# pds.net
KiCad netlist of a schematic drawn in Altium Designer
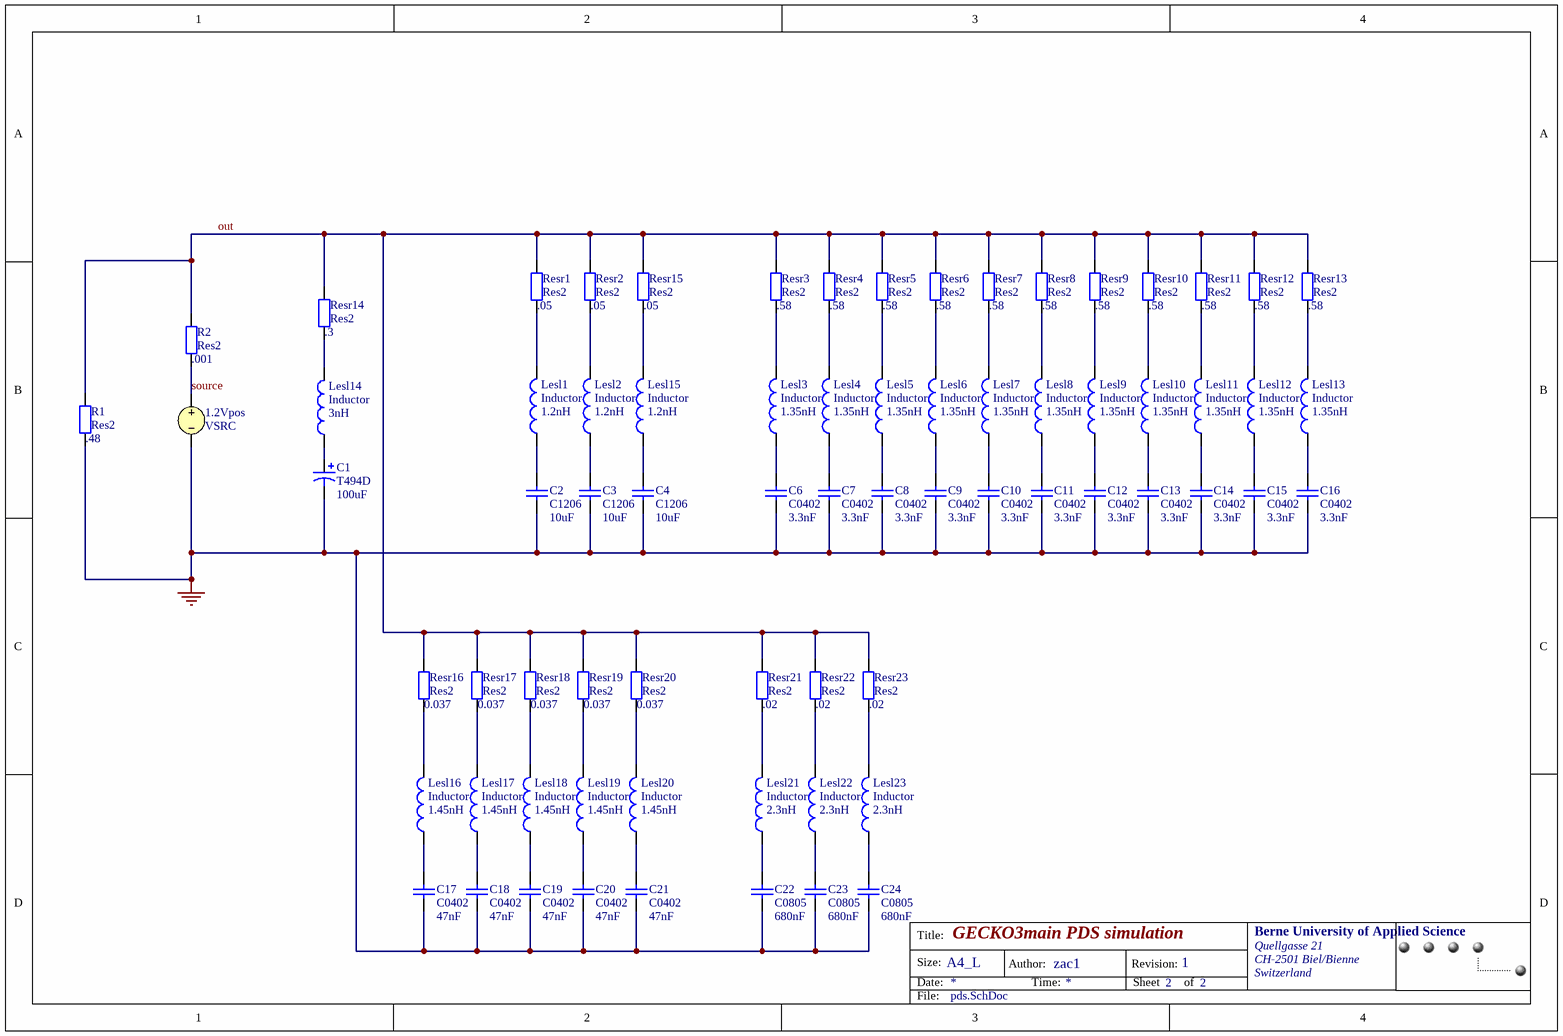
[diagram p0: pds.SchDoc]

(export (version "E")
  (design (tool "Eeschema 10.0.6"))
  (components
    (comp (ref "1.2Vpos")
      (value "VSRC")
      (description "Voltage Source")
      (fields (field (name "PUBLISHER") "Altium Limited"))
      (libsource (lib "Simulation Sources") (part "VSRC"))
    )
    (comp (ref "C1")
      (value "T494D")
      (footprint "D")
      (description "Solid Tantalum Chip Capacitor, Standard T494 Series - Low ESR, Industrial Grade")
      (fields (field (name "ALTIUM_VALUE") "100uF") (field (name "PUBLISHER") "Altium Limited"))
      (libsource (lib "KEMET Chip Capacitor") (part "T494D"))
    )
    (comp (ref "C2")
      (value "C1206")
      (footprint "1206")
      (description "Ceramic Chip Capacitor - Standard")
      (fields (field (name "ALTIUM_VALUE") "10uF") (field (name "PUBLISHER") "Altium Limited"))
      (libsource (lib "KEMET Chip Capacitor") (part "C1206"))
    )
    (comp (ref "C3")
      (value "C1206")
      (footprint "1206")
      (description "Ceramic Chip Capacitor - Standard")
      (fields (field (name "ALTIUM_VALUE") "10uF") (field (name "PUBLISHER") "Altium Limited"))
      (libsource (lib "KEMET Chip Capacitor") (part "C1206"))
    )
    (comp (ref "C4")
      (value "C1206")
      (footprint "1206")
      (description "Ceramic Chip Capacitor - Standard")
      (fields (field (name "ALTIUM_VALUE") "10uF") (field (name "PUBLISHER") "Altium Limited"))
      (libsource (lib "KEMET Chip Capacitor") (part "C1206"))
    )
    (comp (ref "C6")
      (value "C0402")
      (footprint "0402")
      (description "Ceramic Chip Capacitor - Standard")
      (fields (field (name "ALTIUM_VALUE") "3.3nF") (field (name "PUBLISHER") "Altium Limited"))
      (libsource (lib "KEMET Chip Capacitor") (part "C0402"))
    )
    (comp (ref "C7")
      (value "C0402")
      (footprint "0402")
      (description "Ceramic Chip Capacitor - Standard")
      (fields (field (name "ALTIUM_VALUE") "3.3nF") (field (name "PUBLISHER") "Altium Limited"))
      (libsource (lib "KEMET Chip Capacitor") (part "C0402"))
    )
    (comp (ref "C8")
      (value "C0402")
      (footprint "0402")
      (description "Ceramic Chip Capacitor - Standard")
      (fields (field (name "ALTIUM_VALUE") "3.3nF") (field (name "PUBLISHER") "Altium Limited"))
      (libsource (lib "KEMET Chip Capacitor") (part "C0402"))
    )
    (comp (ref "C9")
      (value "C0402")
      (footprint "0402")
      (description "Ceramic Chip Capacitor - Standard")
      (fields (field (name "ALTIUM_VALUE") "3.3nF") (field (name "PUBLISHER") "Altium Limited"))
      (libsource (lib "KEMET Chip Capacitor") (part "C0402"))
    )
    (comp (ref "C10")
      (value "C0402")
      (footprint "0402")
      (description "Ceramic Chip Capacitor - Standard")
      (fields (field (name "ALTIUM_VALUE") "3.3nF") (field (name "PUBLISHER") "Altium Limited"))
      (libsource (lib "KEMET Chip Capacitor") (part "C0402"))
    )
    (comp (ref "C11")
      (value "C0402")
      (footprint "0402")
      (description "Ceramic Chip Capacitor - Standard")
      (fields (field (name "ALTIUM_VALUE") "3.3nF") (field (name "PUBLISHER") "Altium Limited"))
      (libsource (lib "KEMET Chip Capacitor") (part "C0402"))
    )
    (comp (ref "C12")
      (value "C0402")
      (footprint "0402")
      (description "Ceramic Chip Capacitor - Standard")
      (fields (field (name "ALTIUM_VALUE") "3.3nF") (field (name "PUBLISHER") "Altium Limited"))
      (libsource (lib "KEMET Chip Capacitor") (part "C0402"))
    )
    (comp (ref "C13")
      (value "C0402")
      (footprint "0402")
      (description "Ceramic Chip Capacitor - Standard")
      (fields (field (name "ALTIUM_VALUE") "3.3nF") (field (name "PUBLISHER") "Altium Limited"))
      (libsource (lib "KEMET Chip Capacitor") (part "C0402"))
    )
    (comp (ref "C14")
      (value "C0402")
      (footprint "0402")
      (description "Ceramic Chip Capacitor - Standard")
      (fields (field (name "ALTIUM_VALUE") "3.3nF") (field (name "PUBLISHER") "Altium Limited"))
      (libsource (lib "KEMET Chip Capacitor") (part "C0402"))
    )
    (comp (ref "C15")
      (value "C0402")
      (footprint "0402")
      (description "Ceramic Chip Capacitor - Standard")
      (fields (field (name "ALTIUM_VALUE") "3.3nF") (field (name "PUBLISHER") "Altium Limited"))
      (libsource (lib "KEMET Chip Capacitor") (part "C0402"))
    )
    (comp (ref "C16")
      (value "C0402")
      (footprint "0402")
      (description "Ceramic Chip Capacitor - Standard")
      (fields (field (name "ALTIUM_VALUE") "3.3nF") (field (name "PUBLISHER") "Altium Limited"))
      (libsource (lib "KEMET Chip Capacitor") (part "C0402"))
    )
    (comp (ref "C17")
      (value "C0402")
      (footprint "0402")
      (description "Ceramic Chip Capacitor - Standard")
      (fields (field (name "ALTIUM_VALUE") "47nF") (field (name "PUBLISHER") "Altium Limited"))
      (libsource (lib "KEMET Chip Capacitor") (part "C0402"))
    )
    (comp (ref "C18")
      (value "C0402")
      (footprint "0402")
      (description "Ceramic Chip Capacitor - Standard")
      (fields (field (name "ALTIUM_VALUE") "47nF") (field (name "PUBLISHER") "Altium Limited"))
      (libsource (lib "KEMET Chip Capacitor") (part "C0402"))
    )
    (comp (ref "C19")
      (value "C0402")
      (footprint "0402")
      (description "Ceramic Chip Capacitor - Standard")
      (fields (field (name "ALTIUM_VALUE") "47nF") (field (name "PUBLISHER") "Altium Limited"))
      (libsource (lib "KEMET Chip Capacitor") (part "C0402"))
    )
    (comp (ref "C20")
      (value "C0402")
      (footprint "0402")
      (description "Ceramic Chip Capacitor - Standard")
      (fields (field (name "ALTIUM_VALUE") "47nF") (field (name "PUBLISHER") "Altium Limited"))
      (libsource (lib "KEMET Chip Capacitor") (part "C0402"))
    )
    (comp (ref "C21")
      (value "C0402")
      (footprint "0402")
      (description "Ceramic Chip Capacitor - Standard")
      (fields (field (name "ALTIUM_VALUE") "47nF") (field (name "PUBLISHER") "Altium Limited"))
      (libsource (lib "KEMET Chip Capacitor") (part "C0402"))
    )
    (comp (ref "C22")
      (value "C0805")
      (footprint "0805")
      (description "Ceramic Chip Capacitor - Standard")
      (fields (field (name "ALTIUM_VALUE") "680nF") (field (name "PUBLISHER") "Altium Limited"))
      (libsource (lib "KEMET Chip Capacitor") (part "C0805"))
    )
    (comp (ref "C23")
      (value "C0805")
      (footprint "0805")
      (description "Ceramic Chip Capacitor - Standard")
      (fields (field (name "ALTIUM_VALUE") "680nF") (field (name "PUBLISHER") "Altium Limited"))
      (libsource (lib "KEMET Chip Capacitor") (part "C0805"))
    )
    (comp (ref "C24")
      (value "C0805")
      (footprint "0805")
      (description "Ceramic Chip Capacitor - Standard")
      (fields (field (name "ALTIUM_VALUE") "680nF") (field (name "PUBLISHER") "Altium Limited"))
      (libsource (lib "KEMET Chip Capacitor") (part "C0805"))
    )
    (comp (ref "Lesl1")
      (value "Inductor")
      (footprint "INDC1005-0402")
      (fields (field (name "ALTIUM_VALUE") "1.2nH") (field (name "PUBLISHER") "Altium Limited"))
      (libsource (lib "Miscellaneous Devices") (part "Inductor"))
    )
    (comp (ref "Lesl2")
      (value "Inductor")
      (footprint "INDC1005-0402")
      (fields (field (name "ALTIUM_VALUE") "1.2nH") (field (name "PUBLISHER") "Altium Limited"))
      (libsource (lib "Miscellaneous Devices") (part "Inductor"))
    )
    (comp (ref "Lesl3")
      (value "Inductor")
      (footprint "INDC1005-0402")
      (fields (field (name "ALTIUM_VALUE") "1.35nH") (field (name "PUBLISHER") "Altium Limited"))
      (libsource (lib "Miscellaneous Devices") (part "Inductor"))
    )
    (comp (ref "Lesl4")
      (value "Inductor")
      (footprint "INDC1005-0402")
      (fields (field (name "ALTIUM_VALUE") "1.35nH") (field (name "PUBLISHER") "Altium Limited"))
      (libsource (lib "Miscellaneous Devices") (part "Inductor"))
    )
    (comp (ref "Lesl5")
      (value "Inductor")
      (footprint "INDC1005-0402")
      (fields (field (name "ALTIUM_VALUE") "1.35nH") (field (name "PUBLISHER") "Altium Limited"))
      (libsource (lib "Miscellaneous Devices") (part "Inductor"))
    )
    (comp (ref "Lesl6")
      (value "Inductor")
      (footprint "INDC1005-0402")
      (fields (field (name "ALTIUM_VALUE") "1.35nH") (field (name "PUBLISHER") "Altium Limited"))
      (libsource (lib "Miscellaneous Devices") (part "Inductor"))
    )
    (comp (ref "Lesl7")
      (value "Inductor")
      (footprint "INDC1005-0402")
      (fields (field (name "ALTIUM_VALUE") "1.35nH") (field (name "PUBLISHER") "Altium Limited"))
      (libsource (lib "Miscellaneous Devices") (part "Inductor"))
    )
    (comp (ref "Lesl8")
      (value "Inductor")
      (footprint "INDC1005-0402")
      (fields (field (name "ALTIUM_VALUE") "1.35nH") (field (name "PUBLISHER") "Altium Limited"))
      (libsource (lib "Miscellaneous Devices") (part "Inductor"))
    )
    (comp (ref "Lesl9")
      (value "Inductor")
      (footprint "INDC1005-0402")
      (fields (field (name "ALTIUM_VALUE") "1.35nH") (field (name "PUBLISHER") "Altium Limited"))
      (libsource (lib "Miscellaneous Devices") (part "Inductor"))
    )
    (comp (ref "Lesl10")
      (value "Inductor")
      (footprint "INDC1005-0402")
      (fields (field (name "ALTIUM_VALUE") "1.35nH") (field (name "PUBLISHER") "Altium Limited"))
      (libsource (lib "Miscellaneous Devices") (part "Inductor"))
    )
    (comp (ref "Lesl11")
      (value "Inductor")
      (footprint "INDC1005-0402")
      (fields (field (name "ALTIUM_VALUE") "1.35nH") (field (name "PUBLISHER") "Altium Limited"))
      (libsource (lib "Miscellaneous Devices") (part "Inductor"))
    )
    (comp (ref "Lesl12")
      (value "Inductor")
      (footprint "INDC1005-0402")
      (fields (field (name "ALTIUM_VALUE") "1.35nH") (field (name "PUBLISHER") "Altium Limited"))
      (libsource (lib "Miscellaneous Devices") (part "Inductor"))
    )
    (comp (ref "Lesl13")
      (value "Inductor")
      (footprint "INDC1005-0402")
      (fields (field (name "ALTIUM_VALUE") "1.35nH") (field (name "PUBLISHER") "Altium Limited"))
      (libsource (lib "Miscellaneous Devices") (part "Inductor"))
    )
    (comp (ref "Lesl14")
      (value "Inductor")
      (footprint "INDC1005-0402")
      (fields (field (name "ALTIUM_VALUE") "3nH") (field (name "PUBLISHER") "Altium Limited"))
      (libsource (lib "Miscellaneous Devices") (part "Inductor"))
    )
    (comp (ref "Lesl15")
      (value "Inductor")
      (footprint "INDC1005-0402")
      (fields (field (name "ALTIUM_VALUE") "1.2nH") (field (name "PUBLISHER") "Altium Limited"))
      (libsource (lib "Miscellaneous Devices") (part "Inductor"))
    )
    (comp (ref "Lesl16")
      (value "Inductor")
      (footprint "INDC1005-0402")
      (fields (field (name "ALTIUM_VALUE") "1.45nH") (field (name "PUBLISHER") "Altium Limited"))
      (libsource (lib "Miscellaneous Devices") (part "Inductor"))
    )
    (comp (ref "Lesl17")
      (value "Inductor")
      (footprint "INDC1005-0402")
      (fields (field (name "ALTIUM_VALUE") "1.45nH") (field (name "PUBLISHER") "Altium Limited"))
      (libsource (lib "Miscellaneous Devices") (part "Inductor"))
    )
    (comp (ref "Lesl18")
      (value "Inductor")
      (footprint "INDC1005-0402")
      (fields (field (name "ALTIUM_VALUE") "1.45nH") (field (name "PUBLISHER") "Altium Limited"))
      (libsource (lib "Miscellaneous Devices") (part "Inductor"))
    )
    (comp (ref "Lesl19")
      (value "Inductor")
      (footprint "INDC1005-0402")
      (fields (field (name "ALTIUM_VALUE") "1.45nH") (field (name "PUBLISHER") "Altium Limited"))
      (libsource (lib "Miscellaneous Devices") (part "Inductor"))
    )
    (comp (ref "Lesl20")
      (value "Inductor")
      (footprint "INDC1005-0402")
      (fields (field (name "ALTIUM_VALUE") "1.45nH") (field (name "PUBLISHER") "Altium Limited"))
      (libsource (lib "Miscellaneous Devices") (part "Inductor"))
    )
    (comp (ref "Lesl21")
      (value "Inductor")
      (footprint "INDC1005-0402")
      (fields (field (name "ALTIUM_VALUE") "2.3nH") (field (name "PUBLISHER") "Altium Limited"))
      (libsource (lib "Miscellaneous Devices") (part "Inductor"))
    )
    (comp (ref "Lesl22")
      (value "Inductor")
      (footprint "INDC1005-0402")
      (fields (field (name "ALTIUM_VALUE") "2.3nH") (field (name "PUBLISHER") "Altium Limited"))
      (libsource (lib "Miscellaneous Devices") (part "Inductor"))
    )
    (comp (ref "Lesl23")
      (value "Inductor")
      (footprint "INDC1005-0402")
      (fields (field (name "ALTIUM_VALUE") "2.3nH") (field (name "PUBLISHER") "Altium Limited"))
      (libsource (lib "Miscellaneous Devices") (part "Inductor"))
    )
    (comp (ref "R1")
      (value "Res2")
      (footprint "AXIAL-0.4")
      (description "Resistor")
      (fields (field (name "ALTIUM_VALUE") ".48") (field (name "PUBLISHER") "Altium Limited"))
      (libsource (lib "Miscellaneous Devices") (part "Res2"))
    )
    (comp (ref "R2")
      (value "Res2")
      (footprint "AXIAL-0.4")
      (description "Resistor")
      (fields (field (name "ALTIUM_VALUE") ".001") (field (name "PUBLISHER") "Altium Limited"))
      (libsource (lib "Miscellaneous Devices") (part "Res2"))
    )
    (comp (ref "Resr1")
      (value "Res2")
      (footprint "AXIAL-0.4")
      (description "Resistor")
      (fields (field (name "ALTIUM_VALUE") ".05") (field (name "PUBLISHER") "Altium Limited"))
      (libsource (lib "Miscellaneous Devices") (part "Res2"))
    )
    (comp (ref "Resr2")
      (value "Res2")
      (footprint "AXIAL-0.4")
      (description "Resistor")
      (fields (field (name "ALTIUM_VALUE") ".05") (field (name "PUBLISHER") "Altium Limited"))
      (libsource (lib "Miscellaneous Devices") (part "Res2"))
    )
    (comp (ref "Resr3")
      (value "Res2")
      (footprint "AXIAL-0.4")
      (description "Resistor")
      (fields (field (name "ALTIUM_VALUE") ".58") (field (name "PUBLISHER") "Altium Limited"))
      (libsource (lib "Miscellaneous Devices") (part "Res2"))
    )
    (comp (ref "Resr4")
      (value "Res2")
      (footprint "AXIAL-0.4")
      (description "Resistor")
      (fields (field (name "ALTIUM_VALUE") ".58") (field (name "PUBLISHER") "Altium Limited"))
      (libsource (lib "Miscellaneous Devices") (part "Res2"))
    )
    (comp (ref "Resr5")
      (value "Res2")
      (footprint "AXIAL-0.4")
      (description "Resistor")
      (fields (field (name "ALTIUM_VALUE") ".58") (field (name "PUBLISHER") "Altium Limited"))
      (libsource (lib "Miscellaneous Devices") (part "Res2"))
    )
    (comp (ref "Resr6")
      (value "Res2")
      (footprint "AXIAL-0.4")
      (description "Resistor")
      (fields (field (name "ALTIUM_VALUE") ".58") (field (name "PUBLISHER") "Altium Limited"))
      (libsource (lib "Miscellaneous Devices") (part "Res2"))
    )
    (comp (ref "Resr7")
      (value "Res2")
      (footprint "AXIAL-0.4")
      (description "Resistor")
      (fields (field (name "ALTIUM_VALUE") ".58") (field (name "PUBLISHER") "Altium Limited"))
      (libsource (lib "Miscellaneous Devices") (part "Res2"))
    )
    (comp (ref "Resr8")
      (value "Res2")
      (footprint "AXIAL-0.4")
      (description "Resistor")
      (fields (field (name "ALTIUM_VALUE") ".58") (field (name "PUBLISHER") "Altium Limited"))
      (libsource (lib "Miscellaneous Devices") (part "Res2"))
    )
    (comp (ref "Resr9")
      (value "Res2")
      (footprint "AXIAL-0.4")
      (description "Resistor")
      (fields (field (name "ALTIUM_VALUE") ".58") (field (name "PUBLISHER") "Altium Limited"))
      (libsource (lib "Miscellaneous Devices") (part "Res2"))
    )
    (comp (ref "Resr10")
      (value "Res2")
      (footprint "AXIAL-0.4")
      (description "Resistor")
      (fields (field (name "ALTIUM_VALUE") ".58") (field (name "PUBLISHER") "Altium Limited"))
      (libsource (lib "Miscellaneous Devices") (part "Res2"))
    )
    (comp (ref "Resr11")
      (value "Res2")
      (footprint "AXIAL-0.4")
      (description "Resistor")
      (fields (field (name "ALTIUM_VALUE") ".58") (field (name "PUBLISHER") "Altium Limited"))
      (libsource (lib "Miscellaneous Devices") (part "Res2"))
    )
    (comp (ref "Resr12")
      (value "Res2")
      (footprint "AXIAL-0.4")
      (description "Resistor")
      (fields (field (name "ALTIUM_VALUE") ".58") (field (name "PUBLISHER") "Altium Limited"))
      (libsource (lib "Miscellaneous Devices") (part "Res2"))
    )
    (comp (ref "Resr13")
      (value "Res2")
      (footprint "AXIAL-0.4")
      (description "Resistor")
      (fields (field (name "ALTIUM_VALUE") ".58") (field (name "PUBLISHER") "Altium Limited"))
      (libsource (lib "Miscellaneous Devices") (part "Res2"))
    )
    (comp (ref "Resr14")
      (value "Res2")
      (footprint "AXIAL-0.4")
      (description "Resistor")
      (fields (field (name "ALTIUM_VALUE") ".3") (field (name "PUBLISHER") "Altium Limited"))
      (libsource (lib "Miscellaneous Devices") (part "Res2"))
    )
    (comp (ref "Resr15")
      (value "Res2")
      (footprint "AXIAL-0.4")
      (description "Resistor")
      (fields (field (name "ALTIUM_VALUE") ".05") (field (name "PUBLISHER") "Altium Limited"))
      (libsource (lib "Miscellaneous Devices") (part "Res2"))
    )
    (comp (ref "Resr16")
      (value "Res2")
      (footprint "AXIAL-0.4")
      (description "Resistor")
      (fields (field (name "ALTIUM_VALUE") "0.037") (field (name "PUBLISHER") "Altium Limited"))
      (libsource (lib "Miscellaneous Devices") (part "Res2"))
    )
    (comp (ref "Resr17")
      (value "Res2")
      (footprint "AXIAL-0.4")
      (description "Resistor")
      (fields (field (name "ALTIUM_VALUE") "0.037") (field (name "PUBLISHER") "Altium Limited"))
      (libsource (lib "Miscellaneous Devices") (part "Res2"))
    )
    (comp (ref "Resr18")
      (value "Res2")
      (footprint "AXIAL-0.4")
      (description "Resistor")
      (fields (field (name "ALTIUM_VALUE") "0.037") (field (name "PUBLISHER") "Altium Limited"))
      (libsource (lib "Miscellaneous Devices") (part "Res2"))
    )
    (comp (ref "Resr19")
      (value "Res2")
      (footprint "AXIAL-0.4")
      (description "Resistor")
      (fields (field (name "ALTIUM_VALUE") "0.037") (field (name "PUBLISHER") "Altium Limited"))
      (libsource (lib "Miscellaneous Devices") (part "Res2"))
    )
    (comp (ref "Resr20")
      (value "Res2")
      (footprint "AXIAL-0.4")
      (description "Resistor")
      (fields (field (name "ALTIUM_VALUE") "0.037") (field (name "PUBLISHER") "Altium Limited"))
      (libsource (lib "Miscellaneous Devices") (part "Res2"))
    )
    (comp (ref "Resr21")
      (value "Res2")
      (footprint "AXIAL-0.4")
      (description "Resistor")
      (fields (field (name "ALTIUM_VALUE") ".02") (field (name "PUBLISHER") "Altium Limited"))
      (libsource (lib "Miscellaneous Devices") (part "Res2"))
    )
    (comp (ref "Resr22")
      (value "Res2")
      (footprint "AXIAL-0.4")
      (description "Resistor")
      (fields (field (name "ALTIUM_VALUE") ".02") (field (name "PUBLISHER") "Altium Limited"))
      (libsource (lib "Miscellaneous Devices") (part "Res2"))
    )
    (comp (ref "Resr23")
      (value "Res2")
      (footprint "AXIAL-0.4")
      (description "Resistor")
      (fields (field (name "ALTIUM_VALUE") ".02") (field (name "PUBLISHER") "Altium Limited"))
      (libsource (lib "Miscellaneous Devices") (part "Res2"))
    )
  )
  (nets
    (net (code "1") (name "/out") (class "Default")
      (node (ref "R1") (pin "2") (pinfunction "2_2") (pintype "passive"))
      (node (ref "R2") (pin "2") (pinfunction "2_2") (pintype "passive"))
      (node (ref "Resr1") (pin "2") (pinfunction "2_2") (pintype "passive"))
      (node (ref "Resr10") (pin "2") (pinfunction "2_2") (pintype "passive"))
      (node (ref "Resr11") (pin "2") (pinfunction "2_2") (pintype "passive"))
      (node (ref "Resr12") (pin "2") (pinfunction "2_2") (pintype "passive"))
      (node (ref "Resr13") (pin "2") (pinfunction "2_2") (pintype "passive"))
      (node (ref "Resr14") (pin "2") (pinfunction "2_2") (pintype "passive"))
      (node (ref "Resr15") (pin "2") (pinfunction "2_2") (pintype "passive"))
      (node (ref "Resr16") (pin "2") (pinfunction "2_2") (pintype "passive"))
      (node (ref "Resr17") (pin "2") (pinfunction "2_2") (pintype "passive"))
      (node (ref "Resr18") (pin "2") (pinfunction "2_2") (pintype "passive"))
      (node (ref "Resr19") (pin "2") (pinfunction "2_2") (pintype "passive"))
      (node (ref "Resr2") (pin "2") (pinfunction "2_2") (pintype "passive"))
      (node (ref "Resr20") (pin "2") (pinfunction "2_2") (pintype "passive"))
      (node (ref "Resr21") (pin "2") (pinfunction "2_2") (pintype "passive"))
      (node (ref "Resr22") (pin "2") (pinfunction "2_2") (pintype "passive"))
      (node (ref "Resr23") (pin "2") (pinfunction "2_2") (pintype "passive"))
      (node (ref "Resr3") (pin "2") (pinfunction "2_2") (pintype "passive"))
      (node (ref "Resr4") (pin "2") (pinfunction "2_2") (pintype "passive"))
      (node (ref "Resr5") (pin "2") (pinfunction "2_2") (pintype "passive"))
      (node (ref "Resr6") (pin "2") (pinfunction "2_2") (pintype "passive"))
      (node (ref "Resr7") (pin "2") (pinfunction "2_2") (pintype "passive"))
      (node (ref "Resr8") (pin "2") (pinfunction "2_2") (pintype "passive"))
      (node (ref "Resr9") (pin "2") (pinfunction "2_2") (pintype "passive"))
    )
    (net (code "2") (name "/source") (class "Default")
      (node (ref "1.2Vpos") (pin "1") (pinfunction "1_1") (pintype "passive"))
      (node (ref "R2") (pin "1") (pinfunction "1_1") (pintype "passive"))
    )
    (net (code "3") (name "GND") (class "Default")
      (node (ref "1.2Vpos") (pin "2") (pinfunction "2_2") (pintype "passive"))
      (node (ref "C1") (pin "2") (pinfunction "2_2") (pintype "passive"))
      (node (ref "C10") (pin "1") (pinfunction "1_1") (pintype "passive"))
      (node (ref "C11") (pin "1") (pinfunction "1_1") (pintype "passive"))
      (node (ref "C12") (pin "1") (pinfunction "1_1") (pintype "passive"))
      (node (ref "C13") (pin "1") (pinfunction "1_1") (pintype "passive"))
      (node (ref "C14") (pin "1") (pinfunction "1_1") (pintype "passive"))
      (node (ref "C15") (pin "1") (pinfunction "1_1") (pintype "passive"))
      (node (ref "C16") (pin "1") (pinfunction "1_1") (pintype "passive"))
      (node (ref "C17") (pin "1") (pinfunction "1_1") (pintype "passive"))
      (node (ref "C18") (pin "1") (pinfunction "1_1") (pintype "passive"))
      (node (ref "C19") (pin "1") (pinfunction "1_1") (pintype "passive"))
      (node (ref "C2") (pin "1") (pinfunction "1_1") (pintype "passive"))
      (node (ref "C20") (pin "1") (pinfunction "1_1") (pintype "passive"))
      (node (ref "C21") (pin "1") (pinfunction "1_1") (pintype "passive"))
      (node (ref "C22") (pin "1") (pinfunction "1_1") (pintype "passive"))
      (node (ref "C23") (pin "1") (pinfunction "1_1") (pintype "passive"))
      (node (ref "C24") (pin "1") (pinfunction "1_1") (pintype "passive"))
      (node (ref "C3") (pin "1") (pinfunction "1_1") (pintype "passive"))
      (node (ref "C4") (pin "1") (pinfunction "1_1") (pintype "passive"))
      (node (ref "C6") (pin "1") (pinfunction "1_1") (pintype "passive"))
      (node (ref "C7") (pin "1") (pinfunction "1_1") (pintype "passive"))
      (node (ref "C8") (pin "1") (pinfunction "1_1") (pintype "passive"))
      (node (ref "C9") (pin "1") (pinfunction "1_1") (pintype "passive"))
      (node (ref "R1") (pin "1") (pinfunction "1_1") (pintype "passive"))
    )
    (net (code "4") (name "Net-(C1-Pad1)") (class "Default")
      (node (ref "C1") (pin "1") (pinfunction "1_1") (pintype "passive"))
      (node (ref "Lesl14") (pin "1") (pinfunction "1_1") (pintype "passive"))
    )
    (net (code "5") (name "Net-(C2-Pad2)") (class "Default")
      (node (ref "C2") (pin "2") (pinfunction "2_2") (pintype "passive"))
      (node (ref "Lesl1") (pin "1") (pinfunction "1_1") (pintype "passive"))
    )
    (net (code "6") (name "Net-(C3-Pad2)") (class "Default")
      (node (ref "C3") (pin "2") (pinfunction "2_2") (pintype "passive"))
      (node (ref "Lesl2") (pin "1") (pinfunction "1_1") (pintype "passive"))
    )
    (net (code "7") (name "Net-(C4-Pad2)") (class "Default")
      (node (ref "C4") (pin "2") (pinfunction "2_2") (pintype "passive"))
      (node (ref "Lesl15") (pin "1") (pinfunction "1_1") (pintype "passive"))
    )
    (net (code "8") (name "Net-(C6-Pad2)") (class "Default")
      (node (ref "C6") (pin "2") (pinfunction "2_2") (pintype "passive"))
      (node (ref "Lesl3") (pin "1") (pinfunction "1_1") (pintype "passive"))
    )
    (net (code "9") (name "Net-(C7-Pad2)") (class "Default")
      (node (ref "C7") (pin "2") (pinfunction "2_2") (pintype "passive"))
      (node (ref "Lesl4") (pin "1") (pinfunction "1_1") (pintype "passive"))
    )
    (net (code "10") (name "Net-(C8-Pad2)") (class "Default")
      (node (ref "C8") (pin "2") (pinfunction "2_2") (pintype "passive"))
      (node (ref "Lesl5") (pin "1") (pinfunction "1_1") (pintype "passive"))
    )
    (net (code "11") (name "Net-(C9-Pad2)") (class "Default")
      (node (ref "C9") (pin "2") (pinfunction "2_2") (pintype "passive"))
      (node (ref "Lesl6") (pin "1") (pinfunction "1_1") (pintype "passive"))
    )
    (net (code "12") (name "Net-(C10-Pad2)") (class "Default")
      (node (ref "C10") (pin "2") (pinfunction "2_2") (pintype "passive"))
      (node (ref "Lesl7") (pin "1") (pinfunction "1_1") (pintype "passive"))
    )
    (net (code "13") (name "Net-(C11-Pad2)") (class "Default")
      (node (ref "C11") (pin "2") (pinfunction "2_2") (pintype "passive"))
      (node (ref "Lesl8") (pin "1") (pinfunction "1_1") (pintype "passive"))
    )
    (net (code "14") (name "Net-(C12-Pad2)") (class "Default")
      (node (ref "C12") (pin "2") (pinfunction "2_2") (pintype "passive"))
      (node (ref "Lesl9") (pin "1") (pinfunction "1_1") (pintype "passive"))
    )
    (net (code "15") (name "Net-(C13-Pad2)") (class "Default")
      (node (ref "C13") (pin "2") (pinfunction "2_2") (pintype "passive"))
      (node (ref "Lesl10") (pin "1") (pinfunction "1_1") (pintype "passive"))
    )
    (net (code "16") (name "Net-(C14-Pad2)") (class "Default")
      (node (ref "C14") (pin "2") (pinfunction "2_2") (pintype "passive"))
      (node (ref "Lesl11") (pin "1") (pinfunction "1_1") (pintype "passive"))
    )
    (net (code "17") (name "Net-(C15-Pad2)") (class "Default")
      (node (ref "C15") (pin "2") (pinfunction "2_2") (pintype "passive"))
      (node (ref "Lesl12") (pin "1") (pinfunction "1_1") (pintype "passive"))
    )
    (net (code "18") (name "Net-(C16-Pad2)") (class "Default")
      (node (ref "C16") (pin "2") (pinfunction "2_2") (pintype "passive"))
      (node (ref "Lesl13") (pin "1") (pinfunction "1_1") (pintype "passive"))
    )
    (net (code "19") (name "Net-(C17-Pad2)") (class "Default")
      (node (ref "C17") (pin "2") (pinfunction "2_2") (pintype "passive"))
      (node (ref "Lesl16") (pin "1") (pinfunction "1_1") (pintype "passive"))
    )
    (net (code "20") (name "Net-(C18-Pad2)") (class "Default")
      (node (ref "C18") (pin "2") (pinfunction "2_2") (pintype "passive"))
      (node (ref "Lesl17") (pin "1") (pinfunction "1_1") (pintype "passive"))
    )
    (net (code "21") (name "Net-(C19-Pad2)") (class "Default")
      (node (ref "C19") (pin "2") (pinfunction "2_2") (pintype "passive"))
      (node (ref "Lesl18") (pin "1") (pinfunction "1_1") (pintype "passive"))
    )
    (net (code "22") (name "Net-(C20-Pad2)") (class "Default")
      (node (ref "C20") (pin "2") (pinfunction "2_2") (pintype "passive"))
      (node (ref "Lesl19") (pin "1") (pinfunction "1_1") (pintype "passive"))
    )
    (net (code "23") (name "Net-(C21-Pad2)") (class "Default")
      (node (ref "C21") (pin "2") (pinfunction "2_2") (pintype "passive"))
      (node (ref "Lesl20") (pin "1") (pinfunction "1_1") (pintype "passive"))
    )
    (net (code "24") (name "Net-(C22-Pad2)") (class "Default")
      (node (ref "C22") (pin "2") (pinfunction "2_2") (pintype "passive"))
      (node (ref "Lesl21") (pin "1") (pinfunction "1_1") (pintype "passive"))
    )
    (net (code "25") (name "Net-(C23-Pad2)") (class "Default")
      (node (ref "C23") (pin "2") (pinfunction "2_2") (pintype "passive"))
      (node (ref "Lesl22") (pin "1") (pinfunction "1_1") (pintype "passive"))
    )
    (net (code "26") (name "Net-(C24-Pad2)") (class "Default")
      (node (ref "C24") (pin "2") (pinfunction "2_2") (pintype "passive"))
      (node (ref "Lesl23") (pin "1") (pinfunction "1_1") (pintype "passive"))
    )
    (net (code "27") (name "Net-(Lesl1-Pad2)") (class "Default")
      (node (ref "Lesl1") (pin "2") (pinfunction "2_2") (pintype "passive"))
      (node (ref "Resr1") (pin "1") (pinfunction "1_1") (pintype "passive"))
    )
    (net (code "28") (name "Net-(Lesl2-Pad2)") (class "Default")
      (node (ref "Lesl2") (pin "2") (pinfunction "2_2") (pintype "passive"))
      (node (ref "Resr2") (pin "1") (pinfunction "1_1") (pintype "passive"))
    )
    (net (code "29") (name "Net-(Lesl3-Pad2)") (class "Default")
      (node (ref "Lesl3") (pin "2") (pinfunction "2_2") (pintype "passive"))
      (node (ref "Resr3") (pin "1") (pinfunction "1_1") (pintype "passive"))
    )
    (net (code "30") (name "Net-(Lesl4-Pad2)") (class "Default")
      (node (ref "Lesl4") (pin "2") (pinfunction "2_2") (pintype "passive"))
      (node (ref "Resr4") (pin "1") (pinfunction "1_1") (pintype "passive"))
    )
    (net (code "31") (name "Net-(Lesl5-Pad2)") (class "Default")
      (node (ref "Lesl5") (pin "2") (pinfunction "2_2") (pintype "passive"))
      (node (ref "Resr5") (pin "1") (pinfunction "1_1") (pintype "passive"))
    )
    (net (code "32") (name "Net-(Lesl6-Pad2)") (class "Default")
      (node (ref "Lesl6") (pin "2") (pinfunction "2_2") (pintype "passive"))
      (node (ref "Resr6") (pin "1") (pinfunction "1_1") (pintype "passive"))
    )
    (net (code "33") (name "Net-(Lesl7-Pad2)") (class "Default")
      (node (ref "Lesl7") (pin "2") (pinfunction "2_2") (pintype "passive"))
      (node (ref "Resr7") (pin "1") (pinfunction "1_1") (pintype "passive"))
    )
    (net (code "34") (name "Net-(Lesl8-Pad2)") (class "Default")
      (node (ref "Lesl8") (pin "2") (pinfunction "2_2") (pintype "passive"))
      (node (ref "Resr8") (pin "1") (pinfunction "1_1") (pintype "passive"))
    )
    (net (code "35") (name "Net-(Lesl9-Pad2)") (class "Default")
      (node (ref "Lesl9") (pin "2") (pinfunction "2_2") (pintype "passive"))
      (node (ref "Resr9") (pin "1") (pinfunction "1_1") (pintype "passive"))
    )
    (net (code "36") (name "Net-(Lesl10-Pad2)") (class "Default")
      (node (ref "Lesl10") (pin "2") (pinfunction "2_2") (pintype "passive"))
      (node (ref "Resr10") (pin "1") (pinfunction "1_1") (pintype "passive"))
    )
    (net (code "37") (name "Net-(Lesl11-Pad2)") (class "Default")
      (node (ref "Lesl11") (pin "2") (pinfunction "2_2") (pintype "passive"))
      (node (ref "Resr11") (pin "1") (pinfunction "1_1") (pintype "passive"))
    )
    (net (code "38") (name "Net-(Lesl12-Pad2)") (class "Default")
      (node (ref "Lesl12") (pin "2") (pinfunction "2_2") (pintype "passive"))
      (node (ref "Resr12") (pin "1") (pinfunction "1_1") (pintype "passive"))
    )
    (net (code "39") (name "Net-(Lesl13-Pad2)") (class "Default")
      (node (ref "Lesl13") (pin "2") (pinfunction "2_2") (pintype "passive"))
      (node (ref "Resr13") (pin "1") (pinfunction "1_1") (pintype "passive"))
    )
    (net (code "40") (name "Net-(Lesl14-Pad2)") (class "Default")
      (node (ref "Lesl14") (pin "2") (pinfunction "2_2") (pintype "passive"))
      (node (ref "Resr14") (pin "1") (pinfunction "1_1") (pintype "passive"))
    )
    (net (code "41") (name "Net-(Lesl15-Pad2)") (class "Default")
      (node (ref "Lesl15") (pin "2") (pinfunction "2_2") (pintype "passive"))
      (node (ref "Resr15") (pin "1") (pinfunction "1_1") (pintype "passive"))
    )
    (net (code "42") (name "Net-(Lesl16-Pad2)") (class "Default")
      (node (ref "Lesl16") (pin "2") (pinfunction "2_2") (pintype "passive"))
      (node (ref "Resr16") (pin "1") (pinfunction "1_1") (pintype "passive"))
    )
    (net (code "43") (name "Net-(Lesl17-Pad2)") (class "Default")
      (node (ref "Lesl17") (pin "2") (pinfunction "2_2") (pintype "passive"))
      (node (ref "Resr17") (pin "1") (pinfunction "1_1") (pintype "passive"))
    )
    (net (code "44") (name "Net-(Lesl18-Pad2)") (class "Default")
      (node (ref "Lesl18") (pin "2") (pinfunction "2_2") (pintype "passive"))
      (node (ref "Resr18") (pin "1") (pinfunction "1_1") (pintype "passive"))
    )
    (net (code "45") (name "Net-(Lesl19-Pad2)") (class "Default")
      (node (ref "Lesl19") (pin "2") (pinfunction "2_2") (pintype "passive"))
      (node (ref "Resr19") (pin "1") (pinfunction "1_1") (pintype "passive"))
    )
    (net (code "46") (name "Net-(Lesl20-Pad2)") (class "Default")
      (node (ref "Lesl20") (pin "2") (pinfunction "2_2") (pintype "passive"))
      (node (ref "Resr20") (pin "1") (pinfunction "1_1") (pintype "passive"))
    )
    (net (code "47") (name "Net-(Lesl21-Pad2)") (class "Default")
      (node (ref "Lesl21") (pin "2") (pinfunction "2_2") (pintype "passive"))
      (node (ref "Resr21") (pin "1") (pinfunction "1_1") (pintype "passive"))
    )
    (net (code "48") (name "Net-(Lesl22-Pad2)") (class "Default")
      (node (ref "Lesl22") (pin "2") (pinfunction "2_2") (pintype "passive"))
      (node (ref "Resr22") (pin "1") (pinfunction "1_1") (pintype "passive"))
    )
    (net (code "49") (name "Net-(Lesl23-Pad2)") (class "Default")
      (node (ref "Lesl23") (pin "2") (pinfunction "2_2") (pintype "passive"))
      (node (ref "Resr23") (pin "1") (pinfunction "1_1") (pintype "passive"))
    )
  )
)
